# 7-WeightSensor.net
KiCad netlist of a schematic drawn in Altium Designer
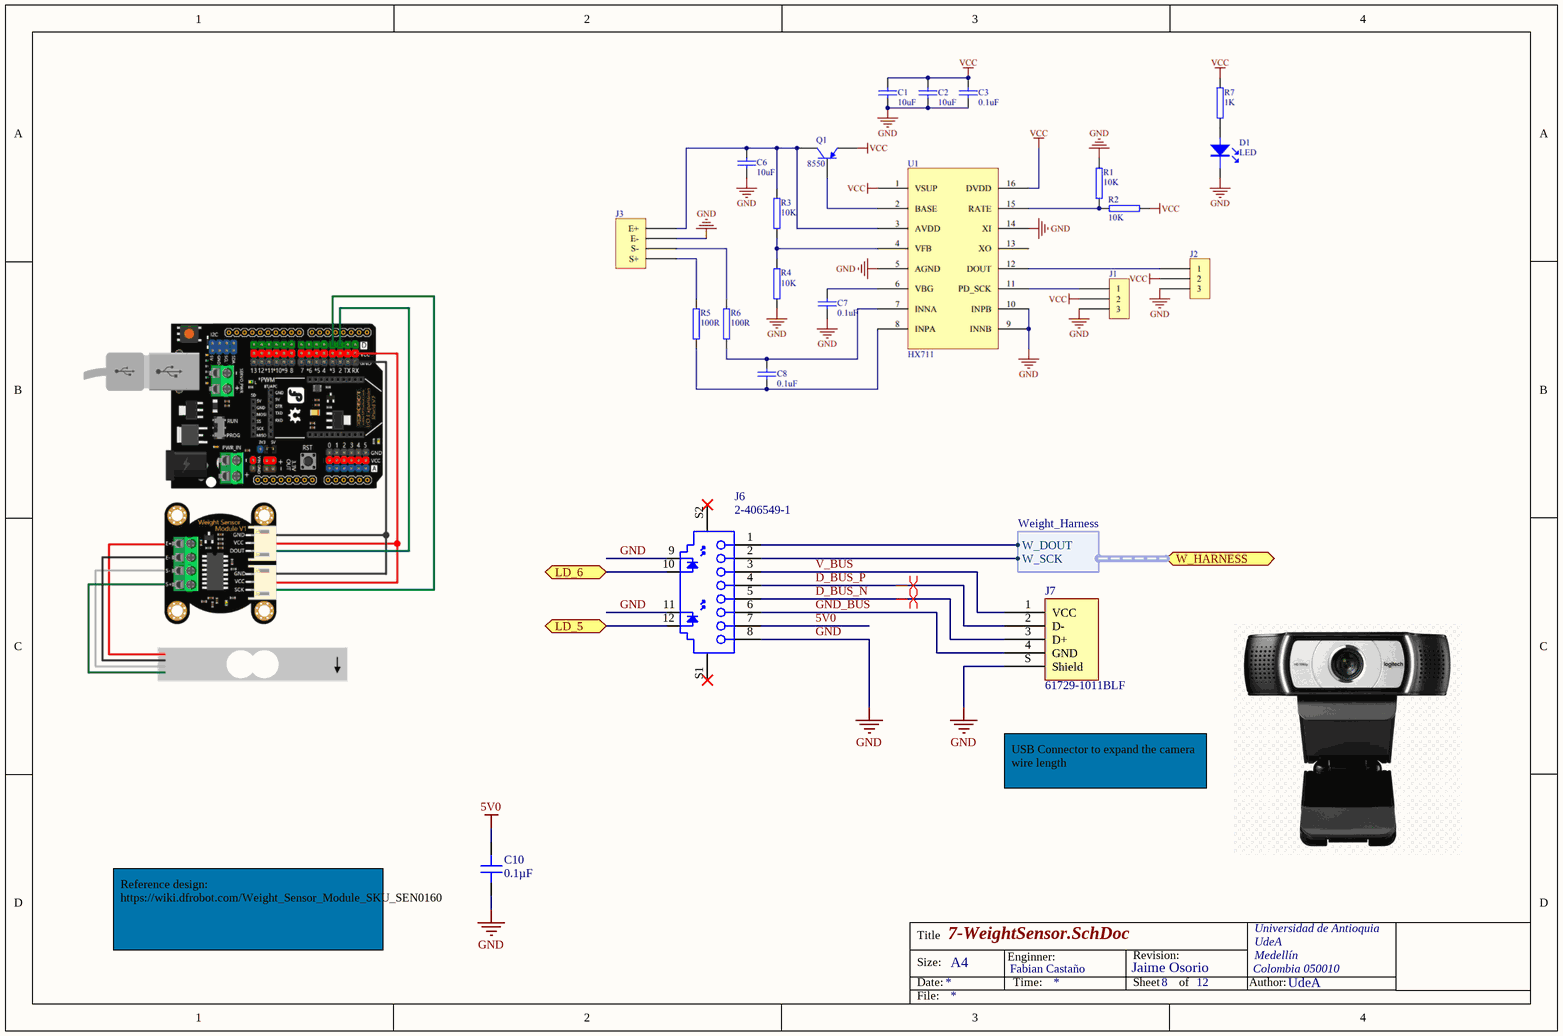
[diagram p0: 7-WeightSensor.SchDoc]

(export (version "E")
  (design (tool "Eeschema 10.0.6"))
  (components
    (comp (ref "C10")
      (value "0.1µF")
      (footprint "CAP 0805_2012")
      (description "CAP CER 0.1UF 50V X7R 0805")
      (fields (field (name "PART NUMBER") "C0805C104M5RACAUTO") (field (name "MANUFACTURER") "KEMET"))
      (libsource (lib "Celestial Altium Library - altium_library") (part "Capacitor"))
    )
    (comp (ref "J6")
      (value "2-406549-1")
      (footprint "TECO-2-406549-1_V")
      (description "RJ45 Connector, Pitch 1.016 mm, 8 Position, Height 14.22 mm, Tail Length 3.18 mm, RoHS, Tray")
      (fields (field (name "MANUFACTURER") "TE Connectivity"))
      (libsource (lib "Altium Content Vault") (part "RJ45-12-2SHLD_A"))
    )
    (comp (ref "J7")
      (value "61729-1011BLF")
      (footprint "FCI USB 61729-1011BLF")
      (description "CONN RCPT USB2.0 TYPEB 4POS R/A")
      (fields
        (field (name "MANUFACTURER") "Amphenol ICC (FCI)")
        (field (name "LASTUPDATED") "9/12/2019 8:52:52 p. m.")
      )
      (libsource (lib "Celestial Altium Library - altium_library") (part "USB 2.0 Type B"))
    )
  )
  (nets
    (net (code "2") (name "/D_BUS_N") (class "Default")
      (node (ref "J6") (pin "5") (pinfunction "5_5") (pintype "passive"))
      (node (ref "J7") (pin "3") (pinfunction "D+_3") (pintype "passive"))
    )
    (net (code "3") (name "/D_BUS_P") (class "Default")
      (node (ref "J6") (pin "4") (pinfunction "4_4") (pintype "passive"))
      (node (ref "J7") (pin "2") (pinfunction "D-_2") (pintype "passive"))
    )
    (net (code "4") (name "/GND_BUS") (class "Default")
      (node (ref "J6") (pin "6") (pinfunction "6_6") (pintype "passive"))
      (node (ref "J7") (pin "4") (pinfunction "GND_4") (pintype "passive"))
    )
    (net (code "5") (name "/LD_5") (class "Default")
      (node (ref "J6") (pin "12") (pinfunction "12_12") (pintype "passive"))
    )
    (net (code "6") (name "/LD_6") (class "Default")
      (node (ref "J6") (pin "10") (pinfunction "10_10") (pintype "passive"))
    )
    (net (code "7") (name "/V_BUS") (class "Default")
      (node (ref "J6") (pin "3") (pinfunction "3_3") (pintype "passive"))
      (node (ref "J7") (pin "1") (pinfunction "VCC_1") (pintype "passive"))
    )
    (net (code "8") (name "/W_DOUT") (class "Default")
      (node (ref "J6") (pin "1") (pinfunction "1_1") (pintype "passive"))
    )
    (net (code "9") (name "/W_SCK") (class "Default")
      (node (ref "J6") (pin "2") (pinfunction "2_2") (pintype "passive"))
    )
    (net (code "11") (name "5V0") (class "Default")
      (node (ref "C10") (pin "2") (pinfunction "2_2") (pintype "passive"))
      (node (ref "J6") (pin "7") (pinfunction "7_7") (pintype "passive"))
    )
    (net (code "12") (name "GND") (class "Default")
      (node (ref "C10") (pin "1") (pinfunction "1_1") (pintype "passive"))
      (node (ref "J6") (pin "11") (pinfunction "11_11") (pintype "passive"))
      (node (ref "J6") (pin "8") (pinfunction "8_8") (pintype "passive"))
      (node (ref "J6") (pin "9") (pinfunction "9_9") (pintype "passive"))
      (node (ref "J7") (pin "S") (pinfunction "Shield_S") (pintype "passive"))
    )
    (net (code "13") (name "unconnected-(J6-PadS1)") (class "Default")
      (node (ref "J6") (pin "S1") (pinfunction "S1_S1") (pintype "passive+no_connect"))
    )
    (net (code "14") (name "unconnected-(J6-PadS2)") (class "Default")
      (node (ref "J6") (pin "S2") (pinfunction "S2_S2") (pintype "passive+no_connect"))
    )
  )
)
